# 7seg-rs485-slave.net
KiCad netlist of a schematic drawn in Altium Designer
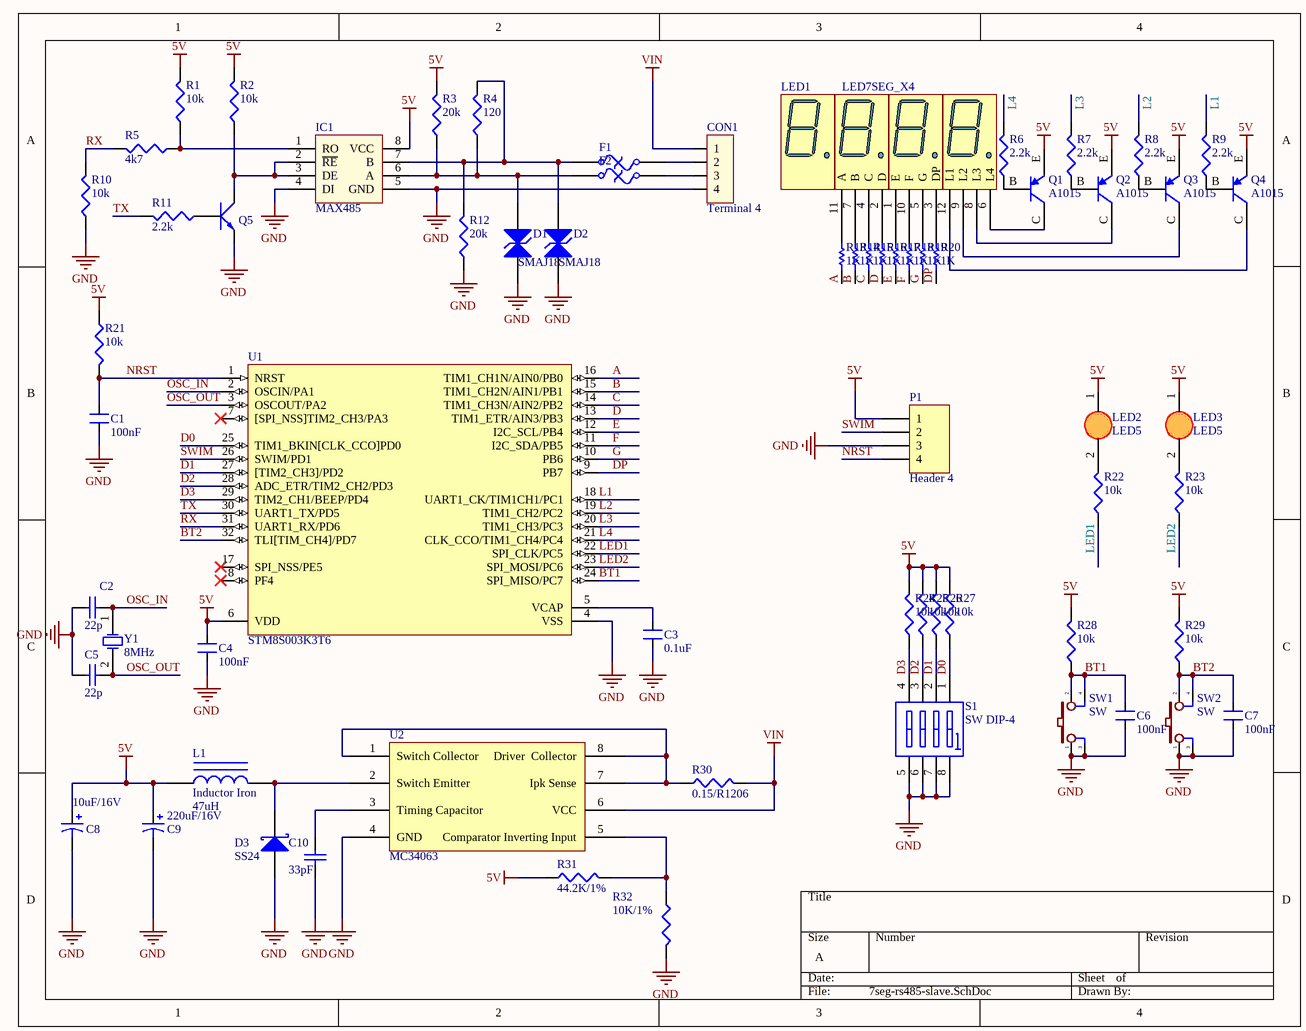
[diagram p0: 7seg-rs485-slave.SchDoc]

(export (version "E")
  (design (tool "Eeschema 10.0.6"))
  (components
    (comp (ref "C1")
      (value "100nF")
      (footprint "PcbLib1:C0805")
      (description "SMD Ceramic  Capacitor")
      (fields (field (name "VOLTAGE") "50V") (field (name "TOLERANCE") "10%"))
      (libsource (lib "ST") (part "CM Ceramic"))
    )
    (comp (ref "C2")
      (value "22p")
      (footprint "C0805")
      (description "Capacitor (Semiconductor SIM Model)")
      (fields (field (name "PUBLISHER") "Altium Limited"))
      (libsource (lib "Miscellaneous Devices") (part "Cap Semi"))
    )
    (comp (ref "C3")
      (value "0.1uF")
      (footprint "PcbLib1:C0805")
      (description "SMD Ceramic  Capacitor")
      (fields (field (name "VOLTAGE") "50V") (field (name "TOLERANCE") "10%"))
      (libsource (lib "ST") (part "CM Ceramic"))
    )
    (comp (ref "C4")
      (value "100nF")
      (footprint "PcbLib1:C0805")
      (description "SMD Ceramic  Capacitor")
      (fields (field (name "VOLTAGE") "50V") (field (name "TOLERANCE") "10%"))
      (libsource (lib "ST") (part "CM Ceramic"))
    )
    (comp (ref "C5")
      (value "22p")
      (footprint "C0805")
      (description "Capacitor (Semiconductor SIM Model)")
      (fields (field (name "PUBLISHER") "Altium Limited"))
      (libsource (lib "Miscellaneous Devices") (part "Cap Semi"))
    )
    (comp (ref "C6")
      (value "100nF")
      (footprint "CM 0805")
      (description "SMD Ceramic  Capacitor")
      (fields (field (name "VOLTAGE") "50V") (field (name "TOLERANCE") "10%"))
      (libsource (lib "ST") (part "CM Ceramic"))
    )
    (comp (ref "C7")
      (value "100nF")
      (footprint "CM 0805")
      (description "SMD Ceramic  Capacitor")
      (fields (field (name "VOLTAGE") "50V") (field (name "TOLERANCE") "10%"))
      (libsource (lib "ST") (part "CM Ceramic"))
    )
    (comp (ref "C8")
      (value "10uF/16V")
      (footprint "Capacitor:C1206")
      (description "Polarized Capacitor (Surface Mount)")
      (fields (field (name "PUBLISHER") "Altium Limited"))
      (libsource (lib "Miscellaneous Devices") (part "Cap Pol3"))
    )
    (comp (ref "C9")
      (value "220uF/16V")
      (footprint "CAPACITOR SIZE_D(D6.6)")
      (description "Polarized Capacitor (Surface Mount)")
      (fields (field (name "PUBLISHER") "Altium Limited"))
      (libsource (lib "Miscellaneous Devices") (part "Cap Pol3"))
    )
    (comp (ref "C10")
      (value "33pF")
      (footprint "PcbLib1:C0805")
      (description "Capacitor 100n 16V 0603")
      (fields (field (name "PUBLISHER") "Altium Limited"))
      (libsource (lib "Capacitor") (part "Cap Semi"))
    )
    (comp (ref "CON1")
      (value "Terminal 4")
      (footprint "PcbLib1:Terminal 4 5.08")
      (libsource (lib "SS_Con") (part "Terminal 4"))
    )
    (comp (ref "D1")
      (value "SMAJ18")
      (footprint "DO-214AC (SMA)")
      (libsource (lib "Schematic") (part "Diode_TVS"))
    )
    (comp (ref "D2")
      (value "SMAJ18")
      (footprint "DO-214AC (SMA)")
      (libsource (lib "Schematic") (part "Diode_TVS"))
    )
    (comp (ref "D3")
      (value "SS24")
      (footprint "DO-214AA")
      (description "Schottky Diode")
      (fields (field (name "PUBLISHER") "Altium Limited"))
      (libsource (lib "Miscellaneous Devices") (part "D Schottky"))
    )
    (comp (ref "F1")
      (value "JK600-150U")
      (footprint "PTC1812")
      (description "Thermal Fuse")
      (fields (field (name "PUBLISHER") "Altium Limited"))
      (libsource (lib "Miscellaneous Devices") (part "Fuse Thermal"))
    )
    (comp (ref "F2")
      (value "JK600-150U")
      (footprint "PTC1812")
      (description "Thermal Fuse")
      (fields (field (name "PUBLISHER") "Altium Limited"))
      (libsource (lib "Miscellaneous Devices") (part "Fuse Thermal"))
    )
    (comp (ref "IC1")
      (value "MAX485")
      (footprint "SO-8")
      (description "RS232 - RS485 (Same sn75176)")
      (libsource (lib "syhaunguyen") (part "MAX485"))
    )
    (comp (ref "L1")
      (value "Inductor Iron")
      (footprint "4848")
      (description "Magnetic-Core Inductor")
      (fields (field (name "ALTIUM_VALUE") "47uH") (field (name "PUBLISHER") "Altium Limited"))
      (libsource (lib "Schematic") (part "Inductor Iron"))
    )
    (comp (ref "LED1")
      (value "LED7SEG_X4")
      (footprint "PcbLib1:7SEGQ")
      (libsource (lib "Schematic") (part "LED7SEG_X4"))
    )
    (comp (ref "LED2")
      (value "LED5")
      (footprint "PcbLib1:LED3MM")
      (description "LED 5mm")
      (libsource (lib "Schematic") (part "LED 5mm"))
    )
    (comp (ref "LED3")
      (value "LED5")
      (footprint "PcbLib1:LED3MM")
      (description "LED 5mm")
      (libsource (lib "Schematic") (part "LED 5mm"))
    )
    (comp (ref "P1")
      (value "Header 4")
      (footprint "PcbLib1:HDR1X4")
      (description "Header, 4-Pin")
      (fields (field (name "PUBLISHER") "Altium Limited"))
      (libsource (lib "SS_Con") (part "Header 4"))
    )
    (comp (ref "Q1")
      (value "A1015")
      (footprint "SC-43-BCE")
      (libsource (lib "Transistor") (part "PNP Transistor"))
    )
    (comp (ref "Q2")
      (value "A1015")
      (footprint "SC-43-BCE")
      (libsource (lib "Transistor") (part "PNP Transistor"))
    )
    (comp (ref "Q3")
      (value "A1015")
      (footprint "SC-43-BCE")
      (libsource (lib "Transistor") (part "PNP Transistor"))
    )
    (comp (ref "Q4")
      (value "A1015")
      (footprint "SC-43-BCE")
      (libsource (lib "Transistor") (part "PNP Transistor"))
    )
    (comp (ref "Q5")
      (value "C1815")
      (footprint "2SC1815")
      (description "NPN SMD Transistor")
      (fields (field (name "MANUFACTURER") "Toshiba"))
      (libsource (lib "ST") (part "C1815"))
    )
    (comp (ref "R1")
      (value "10k")
      (footprint "R0805")
      (description "Resistor")
      (fields
        (field (name "MANUFACTURER") "Vishay / Draloric")
        (field (name "MANUFACTURER PART NUMBER") "RCV0805301KFKEA")
        (field (name "PUBLISHER") "Altium Limited")
      )
      (libsource (lib "altium-import") (part "root_1_Res3_"))
    )
    (comp (ref "R2")
      (value "10k")
      (footprint "R0805")
      (description "Resistor")
      (fields
        (field (name "MANUFACTURER") "Vishay / Draloric")
        (field (name "MANUFACTURER PART NUMBER") "RCV0805301KFKEA")
        (field (name "PUBLISHER") "Altium Limited")
      )
      (libsource (lib "altium-import") (part "root_1_Res3_"))
    )
    (comp (ref "R3")
      (value "20k")
      (footprint "R0805")
      (description "Resistor")
      (fields
        (field (name "MANUFACTURER") "Vishay / Draloric")
        (field (name "MANUFACTURER PART NUMBER") "RCV0805301KFKEA")
        (field (name "PUBLISHER") "Altium Limited")
      )
      (libsource (lib "altium-import") (part "root_1_Res3_"))
    )
    (comp (ref "R4")
      (value "120")
      (footprint "R0805")
      (description "Resistor")
      (fields
        (field (name "MANUFACTURER") "Vishay / Draloric")
        (field (name "MANUFACTURER PART NUMBER") "RCV0805301KFKEA")
        (field (name "PUBLISHER") "Altium Limited")
      )
      (libsource (lib "altium-import") (part "root_1_Res3_"))
    )
    (comp (ref "R5")
      (value "4k7")
      (footprint "R0805")
      (description "Resistor")
      (fields
        (field (name "MANUFACTURER") "Vishay / Draloric")
        (field (name "MANUFACTURER PART NUMBER") "RCV0805301KFKEA")
        (field (name "PUBLISHER") "Altium Limited")
      )
      (libsource (lib "altium-import") (part "root_2_Res3_"))
    )
    (comp (ref "R6")
      (value "2.2k")
      (footprint "R0805")
      (description "Resistor")
      (fields
        (field (name "MANUFACTURER") "Vishay / Draloric")
        (field (name "MANUFACTURER PART NUMBER") "RCV0805301KFKEA")
        (field (name "PUBLISHER") "Altium Limited")
      )
      (libsource (lib "altium-import") (part "root_1_Res3_"))
    )
    (comp (ref "R7")
      (value "2.2k")
      (footprint "R0805")
      (description "Resistor")
      (fields
        (field (name "MANUFACTURER") "Vishay / Draloric")
        (field (name "MANUFACTURER PART NUMBER") "RCV0805301KFKEA")
        (field (name "PUBLISHER") "Altium Limited")
      )
      (libsource (lib "altium-import") (part "root_1_Res3_"))
    )
    (comp (ref "R8")
      (value "2.2k")
      (footprint "R0805")
      (description "Resistor")
      (fields
        (field (name "MANUFACTURER") "Vishay / Draloric")
        (field (name "MANUFACTURER PART NUMBER") "RCV0805301KFKEA")
        (field (name "PUBLISHER") "Altium Limited")
      )
      (libsource (lib "altium-import") (part "root_1_Res3_"))
    )
    (comp (ref "R9")
      (value "2.2k")
      (footprint "R0805")
      (description "Resistor")
      (fields
        (field (name "MANUFACTURER") "Vishay / Draloric")
        (field (name "MANUFACTURER PART NUMBER") "RCV0805301KFKEA")
        (field (name "PUBLISHER") "Altium Limited")
      )
      (libsource (lib "altium-import") (part "root_1_Res3_"))
    )
    (comp (ref "R10")
      (value "10k")
      (footprint "R0805")
      (description "Resistor")
      (fields
        (field (name "MANUFACTURER") "Vishay / Draloric")
        (field (name "MANUFACTURER PART NUMBER") "RCV0805301KFKEA")
        (field (name "PUBLISHER") "Altium Limited")
      )
      (libsource (lib "altium-import") (part "root_1_Res3_"))
    )
    (comp (ref "R11")
      (value "2.2k")
      (footprint "R0805")
      (description "Resistor")
      (fields
        (field (name "MANUFACTURER") "Vishay / Draloric")
        (field (name "MANUFACTURER PART NUMBER") "RCV0805301KFKEA")
        (field (name "PUBLISHER") "Altium Limited")
      )
      (libsource (lib "altium-import") (part "root_2_Res3_"))
    )
    (comp (ref "R12")
      (value "20k")
      (footprint "R0805")
      (description "Resistor")
      (fields
        (field (name "MANUFACTURER") "Vishay / Draloric")
        (field (name "MANUFACTURER PART NUMBER") "RCV0805301KFKEA")
        (field (name "PUBLISHER") "Altium Limited")
      )
      (libsource (lib "altium-import") (part "root_1_Res3_"))
    )
    (comp (ref "R13")
      (value "1K")
      (footprint "R0805")
      (description "RES 120 OHM 1/10W 1% 0603 SMD")
      (fields
        (field (name "DIGI-KEY PART NUMBER") "311-120HRTR-ND")
        (field (name "MANUFACTURER") "Yageo")
        (field (name "PUBLISHER") "Altium Limited")
      )
      (libsource (lib "Miscellaneous Devices") (part "Res1"))
    )
    (comp (ref "R14")
      (value "1K")
      (footprint "R0805")
      (description "RES 120 OHM 1/10W 1% 0603 SMD")
      (fields
        (field (name "DIGI-KEY PART NUMBER") "311-120HRTR-ND")
        (field (name "MANUFACTURER") "Yageo")
        (field (name "PUBLISHER") "Altium Limited")
      )
      (libsource (lib "Miscellaneous Devices") (part "Res1"))
    )
    (comp (ref "R15")
      (value "1K")
      (footprint "R0805")
      (description "RES 120 OHM 1/10W 1% 0603 SMD")
      (fields
        (field (name "DIGI-KEY PART NUMBER") "311-120HRTR-ND")
        (field (name "MANUFACTURER") "Yageo")
        (field (name "PUBLISHER") "Altium Limited")
      )
      (libsource (lib "Miscellaneous Devices") (part "Res1"))
    )
    (comp (ref "R16")
      (value "1K")
      (footprint "R0805")
      (description "RES 120 OHM 1/10W 1% 0603 SMD")
      (fields
        (field (name "DIGI-KEY PART NUMBER") "311-120HRTR-ND")
        (field (name "MANUFACTURER") "Yageo")
        (field (name "PUBLISHER") "Altium Limited")
      )
      (libsource (lib "Miscellaneous Devices") (part "Res1"))
    )
    (comp (ref "R17")
      (value "1K")
      (footprint "R0805")
      (description "RES 120 OHM 1/10W 1% 0603 SMD")
      (fields
        (field (name "DIGI-KEY PART NUMBER") "311-120HRTR-ND")
        (field (name "MANUFACTURER") "Yageo")
        (field (name "PUBLISHER") "Altium Limited")
      )
      (libsource (lib "Miscellaneous Devices") (part "Res1"))
    )
    (comp (ref "R18")
      (value "1K")
      (footprint "R0805")
      (description "RES 120 OHM 1/10W 1% 0603 SMD")
      (fields
        (field (name "DIGI-KEY PART NUMBER") "311-120HRTR-ND")
        (field (name "MANUFACTURER") "Yageo")
        (field (name "PUBLISHER") "Altium Limited")
      )
      (libsource (lib "Miscellaneous Devices") (part "Res1"))
    )
    (comp (ref "R19")
      (value "1K")
      (footprint "R0805")
      (description "RES 120 OHM 1/10W 1% 0603 SMD")
      (fields
        (field (name "DIGI-KEY PART NUMBER") "311-120HRTR-ND")
        (field (name "MANUFACTURER") "Yageo")
        (field (name "PUBLISHER") "Altium Limited")
      )
      (libsource (lib "Miscellaneous Devices") (part "Res1"))
    )
    (comp (ref "R20")
      (value "1K")
      (footprint "R0805")
      (description "RES 120 OHM 1/10W 1% 0603 SMD")
      (fields
        (field (name "DIGI-KEY PART NUMBER") "311-120HRTR-ND")
        (field (name "MANUFACTURER") "Yageo")
        (field (name "PUBLISHER") "Altium Limited")
      )
      (libsource (lib "Miscellaneous Devices") (part "Res1"))
    )
    (comp (ref "R21")
      (value "10k")
      (footprint "R0805")
      (description "Resistor")
      (fields
        (field (name "MANUFACTURER") "Vishay / Draloric")
        (field (name "MANUFACTURER PART NUMBER") "RCV0805301KFKEA")
        (field (name "PUBLISHER") "Altium Limited")
      )
      (libsource (lib "altium-import") (part "root_3_Res3_"))
    )
    (comp (ref "R22")
      (value "10k")
      (footprint "R0805")
      (description "Resistor")
      (fields
        (field (name "MANUFACTURER") "Vishay / Draloric")
        (field (name "MANUFACTURER PART NUMBER") "RCV0805301KFKEA")
        (field (name "PUBLISHER") "Altium Limited")
      )
      (libsource (lib "altium-import") (part "root_1_Res3_"))
    )
    (comp (ref "R23")
      (value "10k")
      (footprint "R0805")
      (description "Resistor")
      (fields
        (field (name "MANUFACTURER") "Vishay / Draloric")
        (field (name "MANUFACTURER PART NUMBER") "RCV0805301KFKEA")
        (field (name "PUBLISHER") "Altium Limited")
      )
      (libsource (lib "altium-import") (part "root_1_Res3_"))
    )
    (comp (ref "R24")
      (value "10k")
      (footprint "R0805")
      (description "Resistor")
      (fields
        (field (name "MANUFACTURER") "Vishay / Draloric")
        (field (name "MANUFACTURER PART NUMBER") "RCV0805301KFKEA")
        (field (name "PUBLISHER") "Altium Limited")
      )
      (libsource (lib "altium-import") (part "root_1_Res3_"))
    )
    (comp (ref "R25")
      (value "10k")
      (footprint "R0805")
      (description "Resistor")
      (fields
        (field (name "MANUFACTURER") "Vishay / Draloric")
        (field (name "MANUFACTURER PART NUMBER") "RCV0805301KFKEA")
        (field (name "PUBLISHER") "Altium Limited")
      )
      (libsource (lib "altium-import") (part "root_1_Res3_"))
    )
    (comp (ref "R26")
      (value "10k")
      (footprint "R0805")
      (description "Resistor")
      (fields
        (field (name "MANUFACTURER") "Vishay / Draloric")
        (field (name "MANUFACTURER PART NUMBER") "RCV0805301KFKEA")
        (field (name "PUBLISHER") "Altium Limited")
      )
      (libsource (lib "altium-import") (part "root_1_Res3_"))
    )
    (comp (ref "R27")
      (value "10k")
      (footprint "R0805")
      (description "Resistor")
      (fields
        (field (name "MANUFACTURER") "Vishay / Draloric")
        (field (name "MANUFACTURER PART NUMBER") "RCV0805301KFKEA")
        (field (name "PUBLISHER") "Altium Limited")
      )
      (libsource (lib "altium-import") (part "root_1_Res3_"))
    )
    (comp (ref "R28")
      (value "10k")
      (footprint "R0805")
      (description "Resistor")
      (fields
        (field (name "MANUFACTURER") "Vishay / Draloric")
        (field (name "MANUFACTURER PART NUMBER") "RCV0805301KFKEA")
        (field (name "PUBLISHER") "Altium Limited")
      )
      (libsource (lib "altium-import") (part "root_1_Res3_"))
    )
    (comp (ref "R29")
      (value "10k")
      (footprint "R0805")
      (description "Resistor")
      (fields
        (field (name "MANUFACTURER") "Vishay / Draloric")
        (field (name "MANUFACTURER PART NUMBER") "RCV0805301KFKEA")
        (field (name "PUBLISHER") "Altium Limited")
      )
      (libsource (lib "altium-import") (part "root_1_Res3_"))
    )
    (comp (ref "R30")
      (value "0.15/R1206")
      (footprint "R1206")
      (description "Resistor 10k 0603")
      (fields (field (name "PUBLISHER") "Altium Limited"))
      (libsource (lib "Miscellaneous Devices") (part "Res3"))
    )
    (comp (ref "R31")
      (value "44.2K/1%")
      (footprint "R0805")
      (description "Resistor 10k 0603")
      (fields (field (name "PUBLISHER") "Altium Limited"))
      (libsource (lib "Miscellaneous Devices") (part "Res3"))
    )
    (comp (ref "R32")
      (value "10K/1%")
      (footprint "R0805")
      (description "Resistor 10k 0603")
      (fields (field (name "PUBLISHER") "Altium Limited"))
      (libsource (lib "Miscellaneous Devices") (part "Res3"))
    )
    (comp (ref "S1")
      (value "SW DIP-4")
      (footprint "PcbLib1:DIP8/W0.3K")
      (description "DIP Switch, 4 Position, SPST")
      (fields (field (name "PUBLISHER") "Altium Limited"))
      (libsource (lib "Miscellaneous Devices") (part "SW DIP-4"))
    )
    (comp (ref "SW1")
      (value "SW")
      (footprint "SW4")
      (description "Switch button 4 pin")
      (libsource (lib "syhaunguyen") (part "SW4-1"))
    )
    (comp (ref "SW2")
      (value "SW")
      (footprint "PcbLib1:SW4")
      (description "Switch button 4 pin")
      (libsource (lib "syhaunguyen") (part "SW4-1"))
    )
    (comp (ref "U1")
      (value "STM8S003K3T6")
      (footprint "PcbLib1:LQFP32_N")
      (libsource (lib "Schlib1") (part "STM8L101K3T6"))
    )
    (comp (ref "U2")
      (value "MC34063")
      (footprint "SO8-150mil")
      (libsource (lib "General IC") (part "MC34063"))
    )
    (comp (ref "Y1")
      (value "8MHz")
      (footprint "SS_Basic:XT2")
      (description "Crystal Oscillator")
      (fields (field (name "PUBLISHER") "Altium Limited"))
      (libsource (lib "Miscellaneous Devices") (part "XTAL"))
    )
  )
  (nets
    (net (code "1") (name "/A") (class "Default")
      (node (ref "R13") (pin "1") (pinfunction "1_1") (pintype "passive"))
      (node (ref "U1") (pin "16") (pinfunction "TIM1_CH1N/AIN0/PB0_16") (pintype "bidirectional"))
    )
    (net (code "2") (name "/B") (class "Default")
      (node (ref "R14") (pin "1") (pinfunction "1_1") (pintype "passive"))
      (node (ref "U1") (pin "15") (pinfunction "TIM1_CH2N/AIN1/PB1_15") (pintype "bidirectional"))
    )
    (net (code "3") (name "/BT1") (class "Default")
      (node (ref "C6") (pin "1") (pinfunction "1_1") (pintype "passive"))
      (node (ref "R28") (pin "1") (pinfunction "1_1") (pintype "passive"))
      (node (ref "SW1") (pin "2") (pinfunction "2_2") (pintype "passive"))
      (node (ref "SW1") (pin "4") (pinfunction "4_4") (pintype "passive"))
      (node (ref "U1") (pin "24") (pinfunction "SPI_MISO/PC7_24") (pintype "bidirectional"))
    )
    (net (code "4") (name "/BT2") (class "Default")
      (node (ref "C7") (pin "1") (pinfunction "1_1") (pintype "passive"))
      (node (ref "R29") (pin "1") (pinfunction "1_1") (pintype "passive"))
      (node (ref "SW2") (pin "2") (pinfunction "2_2") (pintype "passive"))
      (node (ref "SW2") (pin "4") (pinfunction "4_4") (pintype "passive"))
      (node (ref "U1") (pin "32") (pinfunction "TLI[TIM_CH4]/PD7_32") (pintype "bidirectional"))
    )
    (net (code "5") (name "/C") (class "Default")
      (node (ref "R15") (pin "1") (pinfunction "1_1") (pintype "passive"))
      (node (ref "U1") (pin "14") (pinfunction "TIM1_CH3N/AIN2/PB2_14") (pintype "bidirectional"))
    )
    (net (code "6") (name "/D") (class "Default")
      (node (ref "R16") (pin "1") (pinfunction "1_1") (pintype "passive"))
      (node (ref "U1") (pin "13") (pinfunction "TIM1_ETR/AIN3/PB3_13") (pintype "bidirectional"))
    )
    (net (code "7") (name "/D0") (class "Default")
      (node (ref "R27") (pin "1") (pinfunction "1_1") (pintype "passive"))
      (node (ref "S1") (pin "1") (pinfunction "A1_1") (pintype "passive"))
      (node (ref "U1") (pin "25") (pinfunction "TIM1_BKIN[CLK_CCO]PD0_25") (pintype "bidirectional"))
    )
    (net (code "8") (name "/D1") (class "Default")
      (node (ref "R26") (pin "1") (pinfunction "1_1") (pintype "passive"))
      (node (ref "S1") (pin "2") (pinfunction "A2_2") (pintype "passive"))
      (node (ref "U1") (pin "27") (pinfunction "[TIM2_CH3]/PD2_27") (pintype "bidirectional"))
    )
    (net (code "9") (name "/D2") (class "Default")
      (node (ref "R25") (pin "1") (pinfunction "1_1") (pintype "passive"))
      (node (ref "S1") (pin "3") (pinfunction "A3_3") (pintype "passive"))
      (node (ref "U1") (pin "28") (pinfunction "ADC_ETR/TIM2_CH2/PD3_28") (pintype "bidirectional"))
    )
    (net (code "10") (name "/D3") (class "Default")
      (node (ref "R24") (pin "1") (pinfunction "1_1") (pintype "passive"))
      (node (ref "S1") (pin "4") (pinfunction "A4_4") (pintype "passive"))
      (node (ref "U1") (pin "29") (pinfunction "TIM2_CH1/BEEP/PD4_29") (pintype "bidirectional"))
    )
    (net (code "11") (name "/DP") (class "Default")
      (node (ref "R20") (pin "1") (pinfunction "1_1") (pintype "passive"))
      (node (ref "U1") (pin "9") (pinfunction "PB7_9") (pintype "bidirectional"))
    )
    (net (code "12") (name "/E") (class "Default")
      (node (ref "R17") (pin "1") (pinfunction "1_1") (pintype "passive"))
      (node (ref "U1") (pin "12") (pinfunction "I2C_SCL/PB4_12") (pintype "bidirectional"))
    )
    (net (code "13") (name "/F") (class "Default")
      (node (ref "R18") (pin "1") (pinfunction "1_1") (pintype "passive"))
      (node (ref "U1") (pin "11") (pinfunction "I2C_SDA/PB5_11") (pintype "bidirectional"))
    )
    (net (code "14") (name "/G") (class "Default")
      (node (ref "R19") (pin "1") (pinfunction "1_1") (pintype "passive"))
      (node (ref "U1") (pin "10") (pinfunction "PB6_10") (pintype "bidirectional"))
    )
    (net (code "15") (name "/L1") (class "Default")
      (node (ref "R9") (pin "2") (pinfunction "2_2") (pintype "passive"))
      (node (ref "U1") (pin "18") (pinfunction "UART1_CK/TIM1CH1/PC1_18") (pintype "bidirectional"))
    )
    (net (code "16") (name "/L2") (class "Default")
      (node (ref "R8") (pin "2") (pinfunction "2_2") (pintype "passive"))
      (node (ref "U1") (pin "19") (pinfunction "TIM1_CH2/PC2_19") (pintype "bidirectional"))
    )
    (net (code "17") (name "/L3") (class "Default")
      (node (ref "R7") (pin "2") (pinfunction "2_2") (pintype "passive"))
      (node (ref "U1") (pin "20") (pinfunction "TIM1_CH3/PC3_20") (pintype "bidirectional"))
    )
    (net (code "18") (name "/L4") (class "Default")
      (node (ref "R6") (pin "2") (pinfunction "2_2") (pintype "passive"))
      (node (ref "U1") (pin "21") (pinfunction "CLK_CCO/TIM1_CH4/PC4_21") (pintype "bidirectional"))
    )
    (net (code "19") (name "/LED1") (class "Default")
      (node (ref "R22") (pin "1") (pinfunction "1_1") (pintype "passive"))
      (node (ref "U1") (pin "22") (pinfunction "SPI_CLK/PC5_22") (pintype "bidirectional"))
    )
    (net (code "20") (name "/LED2") (class "Default")
      (node (ref "R23") (pin "1") (pinfunction "1_1") (pintype "passive"))
      (node (ref "U1") (pin "23") (pinfunction "SPI_MOSI/PC6_23") (pintype "bidirectional"))
    )
    (net (code "21") (name "/NRST") (class "Default")
      (node (ref "C1") (pin "2") (pinfunction "2_2") (pintype "passive"))
      (node (ref "P1") (pin "4") (pinfunction "4_4") (pintype "passive"))
      (node (ref "R21") (pin "2") (pinfunction "2_2") (pintype "passive"))
      (node (ref "U1") (pin "1") (pinfunction "NRST_1") (pintype "input"))
    )
    (net (code "22") (name "/OSC_IN") (class "Default")
      (node (ref "C2") (pin "2") (pinfunction "2_2") (pintype "passive"))
      (node (ref "U1") (pin "2") (pinfunction "OSCIN/PA1_2") (pintype "bidirectional"))
      (node (ref "Y1") (pin "1") (pinfunction "OSC1_1") (pintype "passive"))
    )
    (net (code "23") (name "/OSC_OUT") (class "Default")
      (node (ref "C5") (pin "2") (pinfunction "2_2") (pintype "passive"))
      (node (ref "U1") (pin "3") (pinfunction "OSCOUT/PA2_3") (pintype "bidirectional"))
      (node (ref "Y1") (pin "2") (pinfunction "OSC2_2") (pintype "passive"))
    )
    (net (code "24") (name "/RX") (class "Default")
      (node (ref "R10") (pin "2") (pinfunction "2_2") (pintype "passive"))
      (node (ref "R5") (pin "2") (pinfunction "2_2") (pintype "passive"))
      (node (ref "U1") (pin "31") (pinfunction "UART1_RX/PD6_31") (pintype "bidirectional"))
    )
    (net (code "25") (name "/SWIM") (class "Default")
      (node (ref "P1") (pin "2") (pinfunction "2_2") (pintype "passive"))
      (node (ref "U1") (pin "26") (pinfunction "SWIM/PD1_26") (pintype "bidirectional"))
    )
    (net (code "26") (name "/TX") (class "Default")
      (node (ref "R11") (pin "2") (pinfunction "2_2") (pintype "passive"))
      (node (ref "U1") (pin "30") (pinfunction "UART1_TX/PD5_30") (pintype "bidirectional"))
    )
    (net (code "27") (name "5V") (class "Default")
      (node (ref "C4") (pin "2") (pinfunction "2_2") (pintype "passive"))
      (node (ref "C8") (pin "1") (pinfunction "1_1") (pintype "passive"))
      (node (ref "C9") (pin "1") (pinfunction "1_1") (pintype "passive"))
      (node (ref "IC1") (pin "8") (pinfunction "VCC_8") (pintype "passive"))
      (node (ref "L1") (pin "1") (pinfunction "1_1") (pintype "passive"))
      (node (ref "LED2") (pin "1") (pinfunction "A_1") (pintype "passive"))
      (node (ref "LED3") (pin "1") (pinfunction "A_1") (pintype "passive"))
      (node (ref "P1") (pin "1") (pinfunction "1_1") (pintype "passive"))
      (node (ref "Q1") (pin "E") (pinfunction "E_E") (pintype "passive"))
      (node (ref "Q2") (pin "E") (pinfunction "E_E") (pintype "passive"))
      (node (ref "Q3") (pin "E") (pinfunction "E_E") (pintype "passive"))
      (node (ref "Q4") (pin "E") (pinfunction "E_E") (pintype "passive"))
      (node (ref "R1") (pin "2") (pinfunction "2_2") (pintype "passive"))
      (node (ref "R2") (pin "2") (pinfunction "2_2") (pintype "passive"))
      (node (ref "R21") (pin "1") (pinfunction "1_1") (pintype "passive"))
      (node (ref "R24") (pin "2") (pinfunction "2_2") (pintype "passive"))
      (node (ref "R25") (pin "2") (pinfunction "2_2") (pintype "passive"))
      (node (ref "R26") (pin "2") (pinfunction "2_2") (pintype "passive"))
      (node (ref "R27") (pin "2") (pinfunction "2_2") (pintype "passive"))
      (node (ref "R28") (pin "2") (pinfunction "2_2") (pintype "passive"))
      (node (ref "R29") (pin "2") (pinfunction "2_2") (pintype "passive"))
      (node (ref "R3") (pin "2") (pinfunction "2_2") (pintype "passive"))
      (node (ref "R31") (pin "1") (pinfunction "1_1") (pintype "passive"))
      (node (ref "U1") (pin "6") (pinfunction "VDD_6") (pintype "power_in"))
    )
    (net (code "28") (name "GND") (class "Default")
      (node (ref "C1") (pin "1") (pinfunction "1_1") (pintype "passive"))
      (node (ref "C10") (pin "2") (pinfunction "2_2") (pintype "passive"))
      (node (ref "C2") (pin "1") (pinfunction "1_1") (pintype "passive"))
      (node (ref "C3") (pin "1") (pinfunction "1_1") (pintype "passive"))
      (node (ref "C4") (pin "1") (pinfunction "1_1") (pintype "passive"))
      (node (ref "C5") (pin "1") (pinfunction "1_1") (pintype "passive"))
      (node (ref "C6") (pin "2") (pinfunction "2_2") (pintype "passive"))
      (node (ref "C7") (pin "2") (pinfunction "2_2") (pintype "passive"))
      (node (ref "C8") (pin "2") (pinfunction "2_2") (pintype "passive"))
      (node (ref "C9") (pin "2") (pinfunction "2_2") (pintype "passive"))
      (node (ref "CON1") (pin "4") (pinfunction "4_4") (pintype "passive"))
      (node (ref "D1") (pin "1") (pinfunction "A_1") (pintype "passive"))
      (node (ref "D2") (pin "1") (pinfunction "A_1") (pintype "passive"))
      (node (ref "D3") (pin "1") (pinfunction "A_1") (pintype "passive"))
      (node (ref "IC1") (pin "4") (pinfunction "DI_4") (pintype "passive"))
      (node (ref "IC1") (pin "5") (pinfunction "GND_5") (pintype "passive"))
      (node (ref "P1") (pin "3") (pinfunction "3_3") (pintype "passive"))
      (node (ref "Q5") (pin "2") (pinfunction "E_2") (pintype "passive"))
      (node (ref "R10") (pin "1") (pinfunction "1_1") (pintype "passive"))
      (node (ref "R12") (pin "1") (pinfunction "1_1") (pintype "passive"))
      (node (ref "R32") (pin "2") (pinfunction "2_2") (pintype "passive"))
      (node (ref "S1") (pin "5") (pinfunction "B4_5") (pintype "passive"))
      (node (ref "S1") (pin "6") (pinfunction "B3_6") (pintype "passive"))
      (node (ref "S1") (pin "7") (pinfunction "B2_7") (pintype "passive"))
      (node (ref "S1") (pin "8") (pinfunction "B1_8") (pintype "passive"))
      (node (ref "SW1") (pin "1") (pinfunction "1_1") (pintype "passive"))
      (node (ref "SW1") (pin "3") (pinfunction "3_3") (pintype "passive"))
      (node (ref "SW2") (pin "1") (pinfunction "1_1") (pintype "passive"))
      (node (ref "SW2") (pin "3") (pinfunction "3_3") (pintype "passive"))
      (node (ref "U1") (pin "4") (pinfunction "VSS_4") (pintype "power_in"))
      (node (ref "U2") (pin "4") (pinfunction "GND_4") (pintype "passive"))
    )
    (net (code "29") (name "Net-(CON1-Pad2)") (class "Default")
      (node (ref "CON1") (pin "2") (pinfunction "2_2") (pintype "passive"))
      (node (ref "F1") (pin "2") (pinfunction "2_2") (pintype "passive"))
    )
    (net (code "30") (name "Net-(CON1-Pad3)") (class "Default")
      (node (ref "CON1") (pin "3") (pinfunction "3_3") (pintype "passive"))
      (node (ref "F2") (pin "2") (pinfunction "2_2") (pintype "passive"))
    )
    (net (code "31") (name "Net-(D1-K)") (class "Default")
      (node (ref "D1") (pin "2") (pinfunction "K_2") (pintype "passive"))
      (node (ref "F2") (pin "1") (pinfunction "1_1") (pintype "passive"))
      (node (ref "IC1") (pin "6") (pinfunction "A_6") (pintype "passive"))
      (node (ref "R3") (pin "1") (pinfunction "1_1") (pintype "passive"))
      (node (ref "R4") (pin "1") (pinfunction "1_1") (pintype "passive"))
    )
    (net (code "32") (name "Net-(D2-K)") (class "Default")
      (node (ref "D2") (pin "2") (pinfunction "K_2") (pintype "passive"))
      (node (ref "F1") (pin "1") (pinfunction "1_1") (pintype "passive"))
      (node (ref "IC1") (pin "7") (pinfunction "B_7") (pintype "passive"))
      (node (ref "R12") (pin "2") (pinfunction "2_2") (pintype "passive"))
      (node (ref "R4") (pin "2") (pinfunction "2_2") (pintype "passive"))
    )
    (net (code "33") (name "Net-(D3-K)") (class "Default")
      (node (ref "D3") (pin "2") (pinfunction "K_2") (pintype "passive"))
      (node (ref "L1") (pin "2") (pinfunction "2_2") (pintype "passive"))
      (node (ref "U2") (pin "2") (pinfunction "Switch_Emitter_2") (pintype "passive"))
    )
    (net (code "34") (name "Net-(IC1-DE)") (class "Default")
      (node (ref "IC1") (pin "2") (pinfunction "~{RE}_2") (pintype "passive"))
      (node (ref "IC1") (pin "3") (pinfunction "DE_3") (pintype "passive"))
      (node (ref "Q5") (pin "3") (pinfunction "C_3") (pintype "passive"))
      (node (ref "R2") (pin "1") (pinfunction "1_1") (pintype "passive"))
    )
    (net (code "35") (name "Net-(IC1-RO)") (class "Default")
      (node (ref "IC1") (pin "1") (pinfunction "RO_1") (pintype "passive"))
      (node (ref "R1") (pin "1") (pinfunction "1_1") (pintype "passive"))
      (node (ref "R5") (pin "1") (pinfunction "1_1") (pintype "passive"))
    )
    (net (code "36") (name "Net-(LED1-A)") (class "Default")
      (node (ref "LED1") (pin "11") (pinfunction "A_11") (pintype "passive"))
      (node (ref "R13") (pin "2") (pinfunction "2_2") (pintype "passive"))
    )
    (net (code "37") (name "Net-(LED1-B)") (class "Default")
      (node (ref "LED1") (pin "7") (pinfunction "B_7") (pintype "passive"))
      (node (ref "R14") (pin "2") (pinfunction "2_2") (pintype "passive"))
    )
    (net (code "38") (name "Net-(LED1-C)") (class "Default")
      (node (ref "LED1") (pin "4") (pinfunction "C_4") (pintype "passive"))
      (node (ref "R15") (pin "2") (pinfunction "2_2") (pintype "passive"))
    )
    (net (code "39") (name "Net-(LED1-D)") (class "Default")
      (node (ref "LED1") (pin "2") (pinfunction "D_2") (pintype "passive"))
      (node (ref "R16") (pin "2") (pinfunction "2_2") (pintype "passive"))
    )
    (net (code "40") (name "Net-(LED1-DP)") (class "Default")
      (node (ref "LED1") (pin "3") (pinfunction "DP_3") (pintype "passive"))
      (node (ref "R20") (pin "2") (pinfunction "2_2") (pintype "passive"))
    )
    (net (code "41") (name "Net-(LED1-E)") (class "Default")
      (node (ref "LED1") (pin "1") (pinfunction "E_1") (pintype "passive"))
      (node (ref "R17") (pin "2") (pinfunction "2_2") (pintype "passive"))
    )
    (net (code "42") (name "Net-(LED1-F)") (class "Default")
      (node (ref "LED1") (pin "10") (pinfunction "F_10") (pintype "passive"))
      (node (ref "R18") (pin "2") (pinfunction "2_2") (pintype "passive"))
    )
    (net (code "43") (name "Net-(LED1-G)") (class "Default")
      (node (ref "LED1") (pin "5") (pinfunction "G_5") (pintype "passive"))
      (node (ref "R19") (pin "2") (pinfunction "2_2") (pintype "passive"))
    )
    (net (code "44") (name "Net-(LED1-L1)") (class "Default")
      (node (ref "LED1") (pin "12") (pinfunction "L1_12") (pintype "passive"))
      (node (ref "Q4") (pin "C") (pinfunction "C_C") (pintype "passive"))
    )
    (net (code "45") (name "Net-(LED1-L2)") (class "Default")
      (node (ref "LED1") (pin "9") (pinfunction "L2_9") (pintype "passive"))
      (node (ref "Q3") (pin "C") (pinfunction "C_C") (pintype "passive"))
    )
    (net (code "46") (name "Net-(LED1-L3)") (class "Default")
      (node (ref "LED1") (pin "8") (pinfunction "L3_8") (pintype "passive"))
      (node (ref "Q2") (pin "C") (pinfunction "C_C") (pintype "passive"))
    )
    (net (code "47") (name "Net-(LED1-L4)") (class "Default")
      (node (ref "LED1") (pin "6") (pinfunction "L4_6") (pintype "passive"))
      (node (ref "Q1") (pin "C") (pinfunction "C_C") (pintype "passive"))
    )
    (net (code "48") (name "Net-(LED2-K)") (class "Default")
      (node (ref "LED2") (pin "2") (pinfunction "K_2") (pintype "passive"))
      (node (ref "R22") (pin "2") (pinfunction "2_2") (pintype "passive"))
    )
    (net (code "49") (name "Net-(LED3-K)") (class "Default")
      (node (ref "LED3") (pin "2") (pinfunction "K_2") (pintype "passive"))
      (node (ref "R23") (pin "2") (pinfunction "2_2") (pintype "passive"))
    )
    (net (code "50") (name "Net-(Q1-PadB)") (class "Default")
      (node (ref "Q1") (pin "B") (pinfunction "B_B") (pintype "passive"))
      (node (ref "R6") (pin "1") (pinfunction "1_1") (pintype "passive"))
    )
    (net (code "51") (name "Net-(Q2-PadB)") (class "Default")
      (node (ref "Q2") (pin "B") (pinfunction "B_B") (pintype "passive"))
      (node (ref "R7") (pin "1") (pinfunction "1_1") (pintype "passive"))
    )
    (net (code "52") (name "Net-(Q3-PadB)") (class "Default")
      (node (ref "Q3") (pin "B") (pinfunction "B_B") (pintype "passive"))
      (node (ref "R8") (pin "1") (pinfunction "1_1") (pintype "passive"))
    )
    (net (code "53") (name "Net-(Q4-PadB)") (class "Default")
      (node (ref "Q4") (pin "B") (pinfunction "B_B") (pintype "passive"))
      (node (ref "R9") (pin "1") (pinfunction "1_1") (pintype "passive"))
    )
    (net (code "54") (name "Net-(Q5-B)") (class "Default")
      (node (ref "Q5") (pin "1") (pinfunction "B_1") (pintype "passive"))
      (node (ref "R11") (pin "1") (pinfunction "1_1") (pintype "passive"))
    )
    (net (code "55") (name "Net-(U1-VCAP)") (class "Default")
      (node (ref "C3") (pin "2") (pinfunction "2_2") (pintype "passive"))
      (node (ref "U1") (pin "5") (pinfunction "VCAP_5") (pintype "power_in"))
    )
    (net (code "56") (name "Net-(U2-Comparator_Inverting_Input)") (class "Default")
      (node (ref "R31") (pin "2") (pinfunction "2_2") (pintype "passive"))
      (node (ref "R32") (pin "1") (pinfunction "1_1") (pintype "passive"))
      (node (ref "U2") (pin "5") (pinfunction "Comparator_Inverting_Input_5") (pintype "passive"))
    )
    (net (code "57") (name "Net-(U2-Driver__Collector)") (class "Default")
      (node (ref "R30") (pin "1") (pinfunction "1_1") (pintype "passive"))
      (node (ref "U2") (pin "1") (pinfunction "Switch_Collector_1") (pintype "passive"))
      (node (ref "U2") (pin "7") (pinfunction "Ipk_Sense_7") (pintype "passive"))
      (node (ref "U2") (pin "8") (pinfunction "Driver__Collector_8") (pintype "passive"))
    )
    (net (code "58") (name "Net-(U2-Timing_Capacitor)") (class "Default")
      (node (ref "C10") (pin "1") (pinfunction "1_1") (pintype "passive"))
      (node (ref "U2") (pin "3") (pinfunction "Timing_Capacitor_3") (pintype "passive"))
    )
    (net (code "59") (name "VIN") (class "Default")
      (node (ref "CON1") (pin "1") (pinfunction "1_1") (pintype "passive"))
      (node (ref "R30") (pin "2") (pinfunction "2_2") (pintype "passive"))
      (node (ref "U2") (pin "6") (pinfunction "VCC_6") (pintype "passive"))
    )
    (net (code "60") (name "unconnected-(U1-PF4-Pad8)") (class "Default")
      (node (ref "U1") (pin "8") (pinfunction "PF4_8") (pintype "bidirectional+no_connect"))
    )
    (net (code "61") (name "unconnected-(U1-SPI_NSS{slash}PE5-Pad17)") (class "Default")
      (node (ref "U1") (pin "17") (pinfunction "SPI_NSS/PE5_17") (pintype "bidirectional+no_connect"))
    )
    (net (code "62") (name "unconnected-(U1-[SPI_NSS]TIM2_CH3{slash}PA3-Pad7)") (class "Default")
      (node (ref "U1") (pin "7") (pinfunction "[SPI_NSS]TIM2_CH3/PA3_7") (pintype "bidirectional+no_connect"))
    )
  )
)
